# PSFB_top_level.net
KiCad netlist of a schematic drawn in Altium Designer
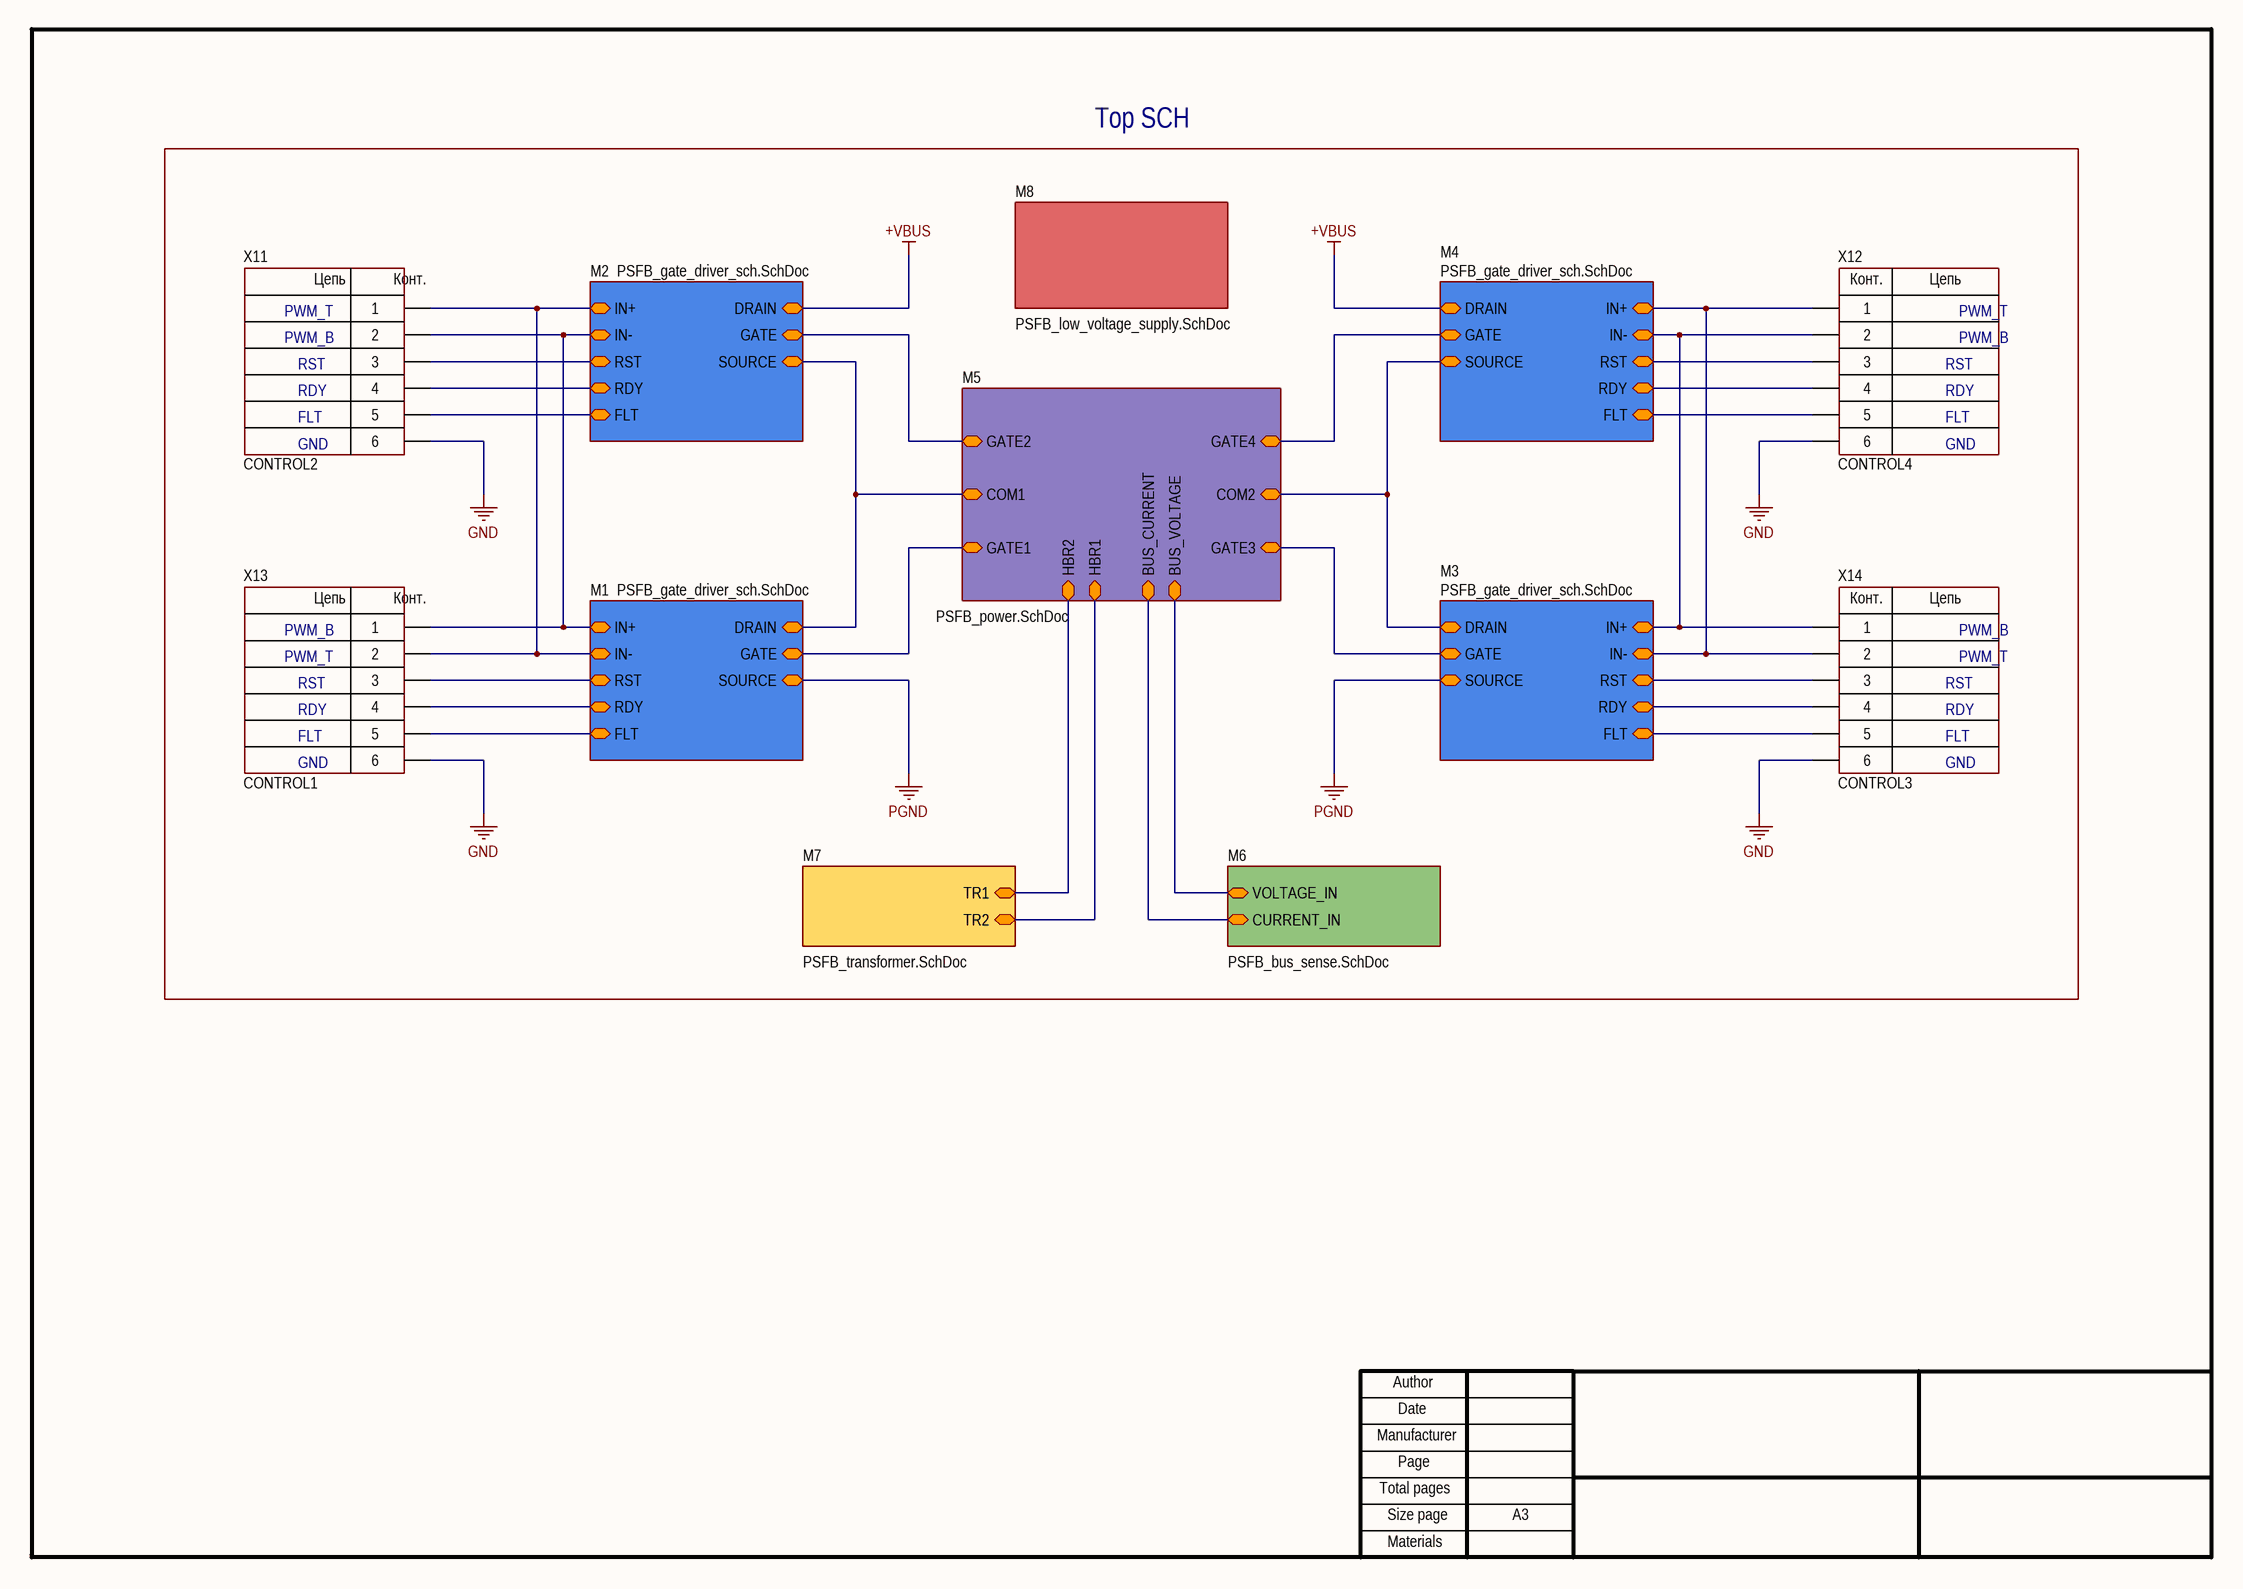
[diagram p0: PSFB_top_level.SchDoc]

(export (version "E")
  (design (tool "Eeschema 10.0.6"))
  (components
    (comp (ref "X11")
      (value "~")
      (footprint "CON: SM06B-GHS")
      (description "Connector Header Surface Mount, Right Angle 6 position 0.039\" (1.00mm)")
      (fields
        (field (name "MANUFACTURER") "JST")
        (field (name "VALUEMANUFACTURERPARTNUMBER") "Connector, 6pin, 1.25mm, 50VDC, 1A")
        (field (name "COMMENTTEXT") "CONTROL2")
      )
      (libsource (lib "") (part "Connector_SM06B_1"))
    )
    (comp (ref "X12")
      (value "~")
      (footprint "CON: SM06B-GHS")
      (description "Connector Header Surface Mount, Right Angle 6 position 0.039\" (1.00mm)")
      (fields
        (field (name "MANUFACTURER") "JST")
        (field (name "VALUEMANUFACTURERPARTNUMBER") "Connector, 6pin, 1.25mm, 50VDC, 1A")
        (field (name "COMMENTTEXT") "CONTROL4")
      )
      (libsource (lib "connector") (part "Connector_SM06B"))
    )
    (comp (ref "X13")
      (value "~")
      (footprint "CON: SM06B-GHS")
      (description "Connector Header Surface Mount, Right Angle 6 position 0.039\" (1.00mm)")
      (fields
        (field (name "MANUFACTURER") "JST")
        (field (name "VALUEMANUFACTURERPARTNUMBER") "Connector, 6pin, 1.25mm, 50VDC, 1A")
        (field (name "COMMENTTEXT") "CONTROL1")
      )
      (libsource (lib "") (part "Connector_SM06B_1"))
    )
    (comp (ref "X14")
      (value "~")
      (footprint "CON: SM06B-GHS")
      (description "Connector Header Surface Mount, Right Angle 6 position 0.039\" (1.00mm)")
      (fields
        (field (name "MANUFACTURER") "JST")
        (field (name "VALUEMANUFACTURERPARTNUMBER") "Connector, 6pin, 1.25mm, 50VDC, 1A")
        (field (name "COMMENTTEXT") "CONTROL3")
      )
      (libsource (lib "connector") (part "Connector_SM06B"))
    )
  )
  (nets
    (net (code "6") (name "/FLT") (class "Default")
      (node (ref "X14") (pin "5") (pinfunction "5_5") (pintype "power_in"))
    )
    (net (code "7") (name "/FLT_1") (class "Default")
      (node (ref "X11") (pin "5") (pinfunction "5_5") (pintype "power_in"))
    )
    (net (code "8") (name "/FLT_2") (class "Default")
      (node (ref "X13") (pin "5") (pinfunction "5_5") (pintype "power_in"))
    )
    (net (code "9") (name "/FLT_3") (class "Default")
      (node (ref "X12") (pin "5") (pinfunction "5_5") (pintype "power_in"))
    )
    (net (code "16") (name "/IN+") (class "Default")
      (node (ref "X12") (pin "2") (pinfunction "2_2") (pintype "passive"))
      (node (ref "X14") (pin "1") (pinfunction "1_1") (pintype "passive"))
    )
    (net (code "17") (name "/IN+_1") (class "Default")
      (node (ref "X11") (pin "1") (pinfunction "1_1") (pintype "passive"))
      (node (ref "X13") (pin "2") (pinfunction "2_2") (pintype "passive"))
    )
    (net (code "18") (name "/IN+_2") (class "Default")
      (node (ref "X11") (pin "2") (pinfunction "2_2") (pintype "passive"))
      (node (ref "X13") (pin "1") (pinfunction "1_1") (pintype "passive"))
    )
    (net (code "19") (name "/IN+_3") (class "Default")
      (node (ref "X12") (pin "1") (pinfunction "1_1") (pintype "passive"))
      (node (ref "X14") (pin "2") (pinfunction "2_2") (pintype "passive"))
    )
    (net (code "20") (name "/RDY") (class "Default")
      (node (ref "X14") (pin "4") (pinfunction "4_4") (pintype "power_in"))
    )
    (net (code "21") (name "/RDY_1") (class "Default")
      (node (ref "X11") (pin "4") (pinfunction "4_4") (pintype "power_in"))
    )
    (net (code "22") (name "/RDY_2") (class "Default")
      (node (ref "X13") (pin "4") (pinfunction "4_4") (pintype "power_in"))
    )
    (net (code "23") (name "/RDY_3") (class "Default")
      (node (ref "X12") (pin "4") (pinfunction "4_4") (pintype "power_in"))
    )
    (net (code "24") (name "/RST") (class "Default")
      (node (ref "X14") (pin "3") (pinfunction "3_3") (pintype "power_in"))
    )
    (net (code "25") (name "/RST_1") (class "Default")
      (node (ref "X11") (pin "3") (pinfunction "3_3") (pintype "power_in"))
    )
    (net (code "26") (name "/RST_2") (class "Default")
      (node (ref "X13") (pin "3") (pinfunction "3_3") (pintype "power_in"))
    )
    (net (code "27") (name "/RST_3") (class "Default")
      (node (ref "X12") (pin "3") (pinfunction "3_3") (pintype "power_in"))
    )
    (net (code "28") (name "GND") (class "Default")
      (node (ref "X11") (pin "6") (pinfunction "6_6") (pintype "power_in"))
      (node (ref "X12") (pin "6") (pinfunction "6_6") (pintype "power_in"))
      (node (ref "X13") (pin "6") (pinfunction "6_6") (pintype "power_in"))
      (node (ref "X14") (pin "6") (pinfunction "6_6") (pintype "power_in"))
    )
  )
)
